# load_cell_amp_JA.net
KiCad netlist of a schematic drawn in EAGLE
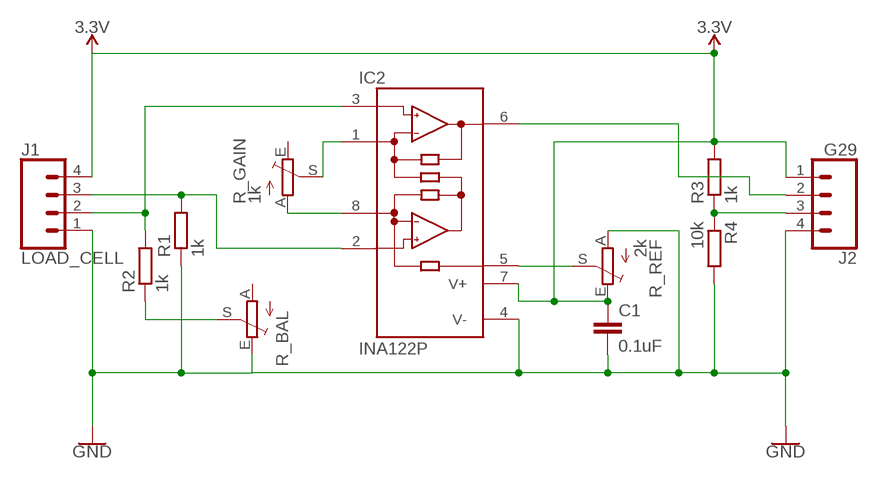
[diagram p0: schematic, sheet 1]

(export (version "E")
  (design (tool "Eeschema 10.0.6"))
  (components
    (comp (ref "C1")
      (value "0.1uF")
      (footprint "eagle-import:C025-024X044")
      (libsource (lib "eagle-import") (part "C-EU025-024X044"))
    )
    (comp (ref "IC2")
      (value "INA122P")
      (footprint "eagle-import:DIL08")
      (fields (field (name "MF") "TEXAS INSTRUMENTS"))
      (libsource (lib "eagle-import") (part "INA122P"))
    )
    (comp (ref "J1")
      (value "LOAD_CELL")
      (footprint "eagle-import:04P")
      (libsource (lib "eagle-import") (part "M04"))
    )
    (comp (ref "J2")
      (value "G29")
      (footprint "eagle-import:04P")
      (libsource (lib "eagle-import") (part "M04"))
    )
    (comp (ref "R1")
      (value "1k")
      (footprint "eagle-import:0207_10")
      (libsource (lib "eagle-import") (part "R-EU_0207/10"))
    )
    (comp (ref "R2")
      (value "1k")
      (footprint "eagle-import:0207_10")
      (libsource (lib "eagle-import") (part "R-EU_0207/10"))
    )
    (comp (ref "R3")
      (value "1k")
      (footprint "eagle-import:0207_10")
      (libsource (lib "eagle-import") (part "R-EU_0207/10"))
    )
    (comp (ref "R4")
      (value "10k")
      (footprint "eagle-import:0207_10")
      (libsource (lib "eagle-import") (part "R-EU_0207/10"))
    )
    (comp (ref "R_BAL")
      (value "10")
      (footprint "eagle-import:RJ9W")
      (libsource (lib "eagle-import") (part "TRIM_EU-RJ9W"))
    )
    (comp (ref "R_GAIN")
      (value "1k")
      (footprint "eagle-import:RJ9W")
      (libsource (lib "eagle-import") (part "TRIM_EU-RJ9W"))
    )
    (comp (ref "R_REF")
      (value "2k")
      (footprint "eagle-import:RJ9W")
      (libsource (lib "eagle-import") (part "TRIM_EU-RJ9W"))
    )
  )
  (nets
    (net (code "1") (name "3.3V") (class "Default")
      (node (ref "C1") (pin "1") (pinfunction "1_1") (pintype "passive"))
      (node (ref "IC2") (pin "7") (pinfunction "V+_7") (pintype "power_in"))
      (node (ref "J1") (pin "4") (pinfunction "4_4") (pintype "passive"))
      (node (ref "J2") (pin "1") (pinfunction "1_1") (pintype "passive"))
      (node (ref "R3") (pin "2") (pinfunction "2_2") (pintype "passive"))
      (node (ref "R_REF") (pin "E") (pinfunction "E_E") (pintype "passive"))
    )
    (net (code "2") (name "GND") (class "Default")
      (node (ref "C1") (pin "2") (pinfunction "2_2") (pintype "passive"))
      (node (ref "IC2") (pin "4") (pinfunction "V-_4") (pintype "power_in"))
      (node (ref "J1") (pin "1") (pinfunction "1_1") (pintype "passive"))
      (node (ref "J2") (pin "4") (pinfunction "4_4") (pintype "passive"))
      (node (ref "R1") (pin "1") (pinfunction "1_1") (pintype "passive"))
      (node (ref "R4") (pin "2") (pinfunction "2_2") (pintype "passive"))
      (node (ref "R_BAL") (pin "E") (pinfunction "E_E") (pintype "passive"))
      (node (ref "R_REF") (pin "A") (pinfunction "A_A") (pintype "passive"))
    )
    (net (code "3") (name "Net-(IC2-+IN)") (class "Default")
      (node (ref "IC2") (pin "3") (pinfunction "+IN_3") (pintype "input"))
      (node (ref "J1") (pin "2") (pinfunction "2_2") (pintype "passive"))
      (node (ref "R2") (pin "2") (pinfunction "2_2") (pintype "passive"))
    )
    (net (code "4") (name "Net-(IC2--IN)") (class "Default")
      (node (ref "IC2") (pin "2") (pinfunction "-IN_2") (pintype "input"))
      (node (ref "J1") (pin "3") (pinfunction "3_3") (pintype "passive"))
      (node (ref "R1") (pin "2") (pinfunction "2_2") (pintype "passive"))
    )
    (net (code "5") (name "Net-(IC2-OUT)") (class "Default")
      (node (ref "IC2") (pin "6") (pinfunction "OUT_6") (pintype "output"))
      (node (ref "J2") (pin "2") (pinfunction "2_2") (pintype "passive"))
    )
    (net (code "6") (name "Net-(IC2-REF)") (class "Default")
      (node (ref "IC2") (pin "5") (pinfunction "REF_5") (pintype "passive"))
      (node (ref "R_REF") (pin "S") (pinfunction "S_S") (pintype "passive"))
    )
    (net (code "7") (name "Net-(IC2-RG-Pad1)") (class "Default")
      (node (ref "IC2") (pin "1") (pinfunction "RG_1") (pintype "passive"))
      (node (ref "R_GAIN") (pin "S") (pinfunction "S_S") (pintype "passive"))
    )
    (net (code "8") (name "Net-(IC2-RG-Pad8)") (class "Default")
      (node (ref "IC2") (pin "8") (pinfunction "RG_8") (pintype "passive"))
      (node (ref "R_GAIN") (pin "A") (pinfunction "A_A") (pintype "passive"))
    )
    (net (code "9") (name "Net-(J2-Pad3)") (class "Default")
      (node (ref "J2") (pin "3") (pinfunction "3_3") (pintype "passive"))
      (node (ref "R3") (pin "1") (pinfunction "1_1") (pintype "passive"))
      (node (ref "R4") (pin "1") (pinfunction "1_1") (pintype "passive"))
    )
    (net (code "10") (name "Net-(R2-Pad1)") (class "Default")
      (node (ref "R2") (pin "1") (pinfunction "1_1") (pintype "passive"))
      (node (ref "R_BAL") (pin "S") (pinfunction "S_S") (pintype "passive"))
    )
    (net (code "11") (name "unconnected-(R_BAL-PadA)") (class "Default")
      (node (ref "R_BAL") (pin "A") (pinfunction "A_A") (pintype "passive"))
    )
    (net (code "12") (name "unconnected-(R_GAIN-PadE)") (class "Default")
      (node (ref "R_GAIN") (pin "E") (pinfunction "E_E") (pintype "passive"))
    )
  )
)
